# SchematicLM386.net
KiCad netlist of a schematic drawn in Altium Designer
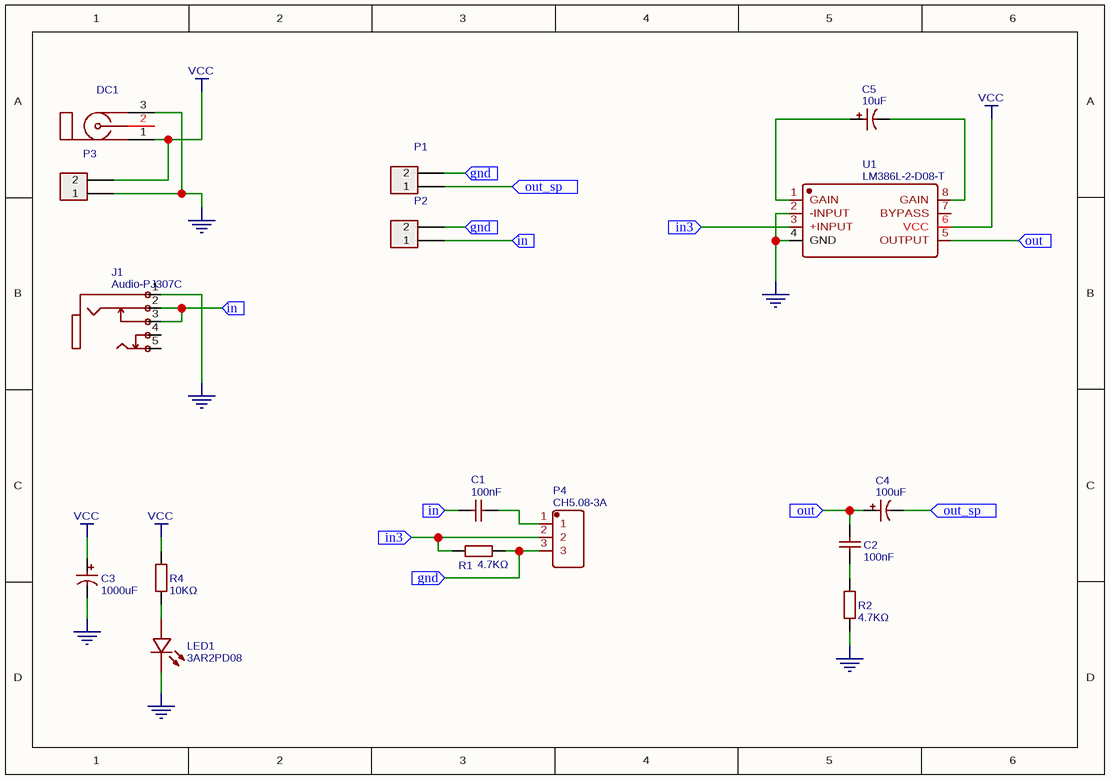
[diagram p0: SchematicLM386.schdoc]

(export (version "E")
  (design (tool "Eeschema 10.0.6"))
  (components
    (comp (ref "C1")
      (value "100nF")
      (fields
        (field (name "VOLTAGE") "50V")
        (field (name "TOLERANCE") "-20%")
        (field (name "BOM_MANUFACTURER PART") "CS1F5.6Y5V1A104Z")
      )
      (libsource (lib "altium-import") (part "root_0_100nF_"))
    )
    (comp (ref "C2")
      (value "100nF")
      (fields
        (field (name "VOLTAGE") "50V")
        (field (name "TOLERANCE") "-20%")
        (field (name "BOM_MANUFACTURER PART") "CS1F5.6Y5V1A104Z")
      )
      (libsource (lib "altium-import") (part "root_1_100nF_"))
    )
    (comp (ref "C3")
      (value "1000uF")
      (fields
        (field (name "VOLTAGE") "25V")
        (field (name "BOM_MANUFACTURER PART") "KM102M025G160A")
        (field (name "BOM_SUPPLIER PART") "C59381")
      )
      (libsource (lib "altium-import") (part "root_3_1000uF_"))
    )
    (comp (ref "C4")
      (value "100uF")
      (fields
        (field (name "VOLTAGE") "50V")
        (field (name "BOM_MANUFACTURER PART") "KM101M050F115A")
        (field (name "BOM_SUPPLIER PART") "C59414")
      )
      (libsource (lib "altium-import") (part "root_0_100uF_"))
    )
    (comp (ref "C5")
      (value "10uF")
      (fields
        (field (name "VOLTAGE") "25V")
        (field (name "BOM_MANUFACTURER PART") "10uF 25V 5*11")
        (field (name "BOM_SUPPLIER PART") "C43347")
      )
      (libsource (lib "altium-import") (part "root_0_10uF_"))
    )
    (comp (ref "DC1")
      (value "DC-005_1")
      (fields
        (field (name "BOM_MANUFACTURER PART") "DC-005Full copper power outlet 2.0mm")
        (field (name "BOM_SUPPLIER PART") "C66437")
      )
      (libsource (lib "altium-import") (part "root_0_DC-005_1_"))
    )
    (comp (ref "J1")
      (value "Audio-PJ307C")
      (fields (field (name "BOM_MANUFACTURER PART") "PJ-307C") (field (name "BOM_SUPPLIER PART") "C16684"))
      (libsource (lib "altium-import") (part "root_0_Audio-PJ307C_"))
    )
    (comp (ref "LED1")
      (value "3AR2PD08")
      (fields (field (name "BOM_SUPPLIER PART") "C13407"))
      (libsource (lib "altium-import") (part "root_3_3AR2PD08_"))
    )
    (comp (ref "P1")
      (value "Header-Female-2.54_1x2")
      (fields (field (name "BOM_SUPPLIER PART") "C49661"))
      (libsource (lib "altium-import") (part "root_2_Header-Female-2.54_1x2_"))
    )
    (comp (ref "P2")
      (value "Header-Female-2.54_1x2")
      (fields (field (name "BOM_SUPPLIER PART") "C49661"))
      (libsource (lib "altium-import") (part "root_2_Header-Female-2.54_1x2_"))
    )
    (comp (ref "P3")
      (value "Header-Female-2.54_1x2")
      (fields (field (name "BOM_SUPPLIER PART") "C49661"))
      (libsource (lib "altium-import") (part "root_2_Header-Female-2.54_1x2_"))
    )
    (comp (ref "P4")
      (value "CH5.08-3A")
      (fields (field (name "BOM_SUPPLIER PART") "C23514"))
      (libsource (lib "altium-import") (part "root_0_CH5.08-3A_"))
    )
    (comp (ref "R1")
      (value "4.7KΩ")
      (fields
        (field (name "POWER") "1/4W")
        (field (name "TOLERANCE") "±1%")
        (field (name "BOM_MANUFACTURER PART") "MFR0W4F4701A50")
      )
      (libsource (lib "altium-import") (part "root_0_4.7KΩ_"))
    )
    (comp (ref "R2")
      (value "4.7KΩ")
      (fields
        (field (name "POWER") "1/4W")
        (field (name "TOLERANCE") "±1%")
        (field (name "BOM_MANUFACTURER PART") "MFR0W4F4701A50")
      )
      (libsource (lib "altium-import") (part "root_1_4.7KΩ_"))
    )
    (comp (ref "R4")
      (value "10KΩ")
      (fields
        (field (name "POWER") "1/4W")
        (field (name "TOLERANCE") "±5%")
        (field (name "BOM_MANUFACTURER PART") "CFR0W4J0103A50")
      )
      (libsource (lib "altium-import") (part "root_1_10KΩ_"))
    )
    (comp (ref "U1")
      (value "LM386L-2-D08-T")
      (fields (field (name "BOM_SUPPLIER PART") "C87306"))
      (libsource (lib "altium-import") (part "root_0_LM386L-2-D08-T_"))
    )
  )
  (nets
    (net (code "1") (name "/gnd") (class "Default")
      (node (ref "P1") (pin "2") (pinfunction "2_2") (pintype "passive"))
      (node (ref "P2") (pin "2") (pinfunction "2_2") (pintype "passive"))
      (node (ref "P4") (pin "3") (pinfunction "3_3") (pintype "passive"))
      (node (ref "R1") (pin "2") (pinfunction "2_2") (pintype "passive"))
    )
    (net (code "2") (name "/in") (class "Default")
      (node (ref "C1") (pin "1") (pinfunction "1_1") (pintype "passive"))
      (node (ref "J1") (pin "2") (pinfunction "2_2") (pintype "passive"))
      (node (ref "J1") (pin "3") (pinfunction "3_3") (pintype "passive"))
      (node (ref "P2") (pin "1") (pinfunction "1_1") (pintype "passive"))
    )
    (net (code "3") (name "/in3") (class "Default")
      (node (ref "P4") (pin "2") (pinfunction "2_2") (pintype "passive"))
      (node (ref "R1") (pin "1") (pinfunction "1_1") (pintype "passive"))
      (node (ref "U1") (pin "3") (pinfunction "+INPUT_3") (pintype "passive"))
    )
    (net (code "4") (name "/out") (class "Default")
      (node (ref "C2") (pin "2") (pinfunction "2_2") (pintype "passive"))
      (node (ref "C4") (pin "1") (pinfunction "1_1") (pintype "passive"))
      (node (ref "U1") (pin "5") (pinfunction "OUTPUT_5") (pintype "passive"))
    )
    (net (code "5") (name "/out_sp") (class "Default")
      (node (ref "C4") (pin "2") (pinfunction "2_2") (pintype "passive"))
      (node (ref "P1") (pin "1") (pinfunction "1_1") (pintype "passive"))
    )
    (net (code "6") (name "GND") (class "Default")
      (node (ref "C3") (pin "2") (pinfunction "2_2") (pintype "passive"))
      (node (ref "DC1") (pin "3") (pinfunction "3_3") (pintype "passive"))
      (node (ref "J1") (pin "1") (pinfunction "1_1") (pintype "passive"))
      (node (ref "LED1") (pin "1") (pinfunction "K_1") (pintype "passive"))
      (node (ref "P3") (pin "1") (pinfunction "1_1") (pintype "passive"))
      (node (ref "R2") (pin "1") (pinfunction "1_1") (pintype "passive"))
      (node (ref "U1") (pin "2") (pinfunction "-INPUT_2") (pintype "passive"))
      (node (ref "U1") (pin "4") (pinfunction "GND_4") (pintype "passive"))
    )
    (net (code "7") (name "Net-(C1-Pad2)") (class "Default")
      (node (ref "C1") (pin "2") (pinfunction "2_2") (pintype "passive"))
      (node (ref "P4") (pin "1") (pinfunction "1_1") (pintype "passive"))
    )
    (net (code "8") (name "Net-(C2-Pad1)") (class "Default")
      (node (ref "C2") (pin "1") (pinfunction "1_1") (pintype "passive"))
      (node (ref "R2") (pin "2") (pinfunction "2_2") (pintype "passive"))
    )
    (net (code "9") (name "Net-(C5-Pad1)") (class "Default")
      (node (ref "C5") (pin "1") (pinfunction "1_1") (pintype "passive"))
      (node (ref "U1") (pin "1") (pinfunction "GAIN_1") (pintype "passive"))
    )
    (net (code "10") (name "Net-(C5-Pad2)") (class "Default")
      (node (ref "C5") (pin "2") (pinfunction "2_2") (pintype "passive"))
      (node (ref "U1") (pin "8") (pinfunction "GAIN_8") (pintype "passive"))
    )
    (net (code "11") (name "Net-(LED1-A)") (class "Default")
      (node (ref "LED1") (pin "2") (pinfunction "A_2") (pintype "passive"))
      (node (ref "R4") (pin "1") (pinfunction "1_1") (pintype "passive"))
    )
    (net (code "12") (name "VCC") (class "Default")
      (node (ref "C3") (pin "1") (pinfunction "1_1") (pintype "passive"))
      (node (ref "DC1") (pin "1") (pinfunction "1_1") (pintype "passive"))
      (node (ref "P3") (pin "2") (pinfunction "2_2") (pintype "passive"))
      (node (ref "R4") (pin "2") (pinfunction "2_2") (pintype "passive"))
      (node (ref "U1") (pin "6") (pinfunction "VCC_6") (pintype "passive"))
    )
    (net (code "13") (name "unconnected-(DC1-VCC-Pad2)") (class "Default")
      (node (ref "DC1") (pin "2") (pinfunction "VCC_2") (pintype "passive"))
    )
    (net (code "14") (name "unconnected-(J1-Pad4)") (class "Default")
      (node (ref "J1") (pin "4") (pinfunction "4_4") (pintype "passive"))
    )
    (net (code "15") (name "unconnected-(J1-Pad5)") (class "Default")
      (node (ref "J1") (pin "5") (pinfunction "5_5") (pintype "passive"))
    )
    (net (code "16") (name "unconnected-(U1-BYPASS-Pad7)") (class "Default")
      (node (ref "U1") (pin "7") (pinfunction "BYPASS_7") (pintype "passive"))
    )
  )
)
